# RH010_1.net
KiCad netlist of a schematic drawn in EAGLE
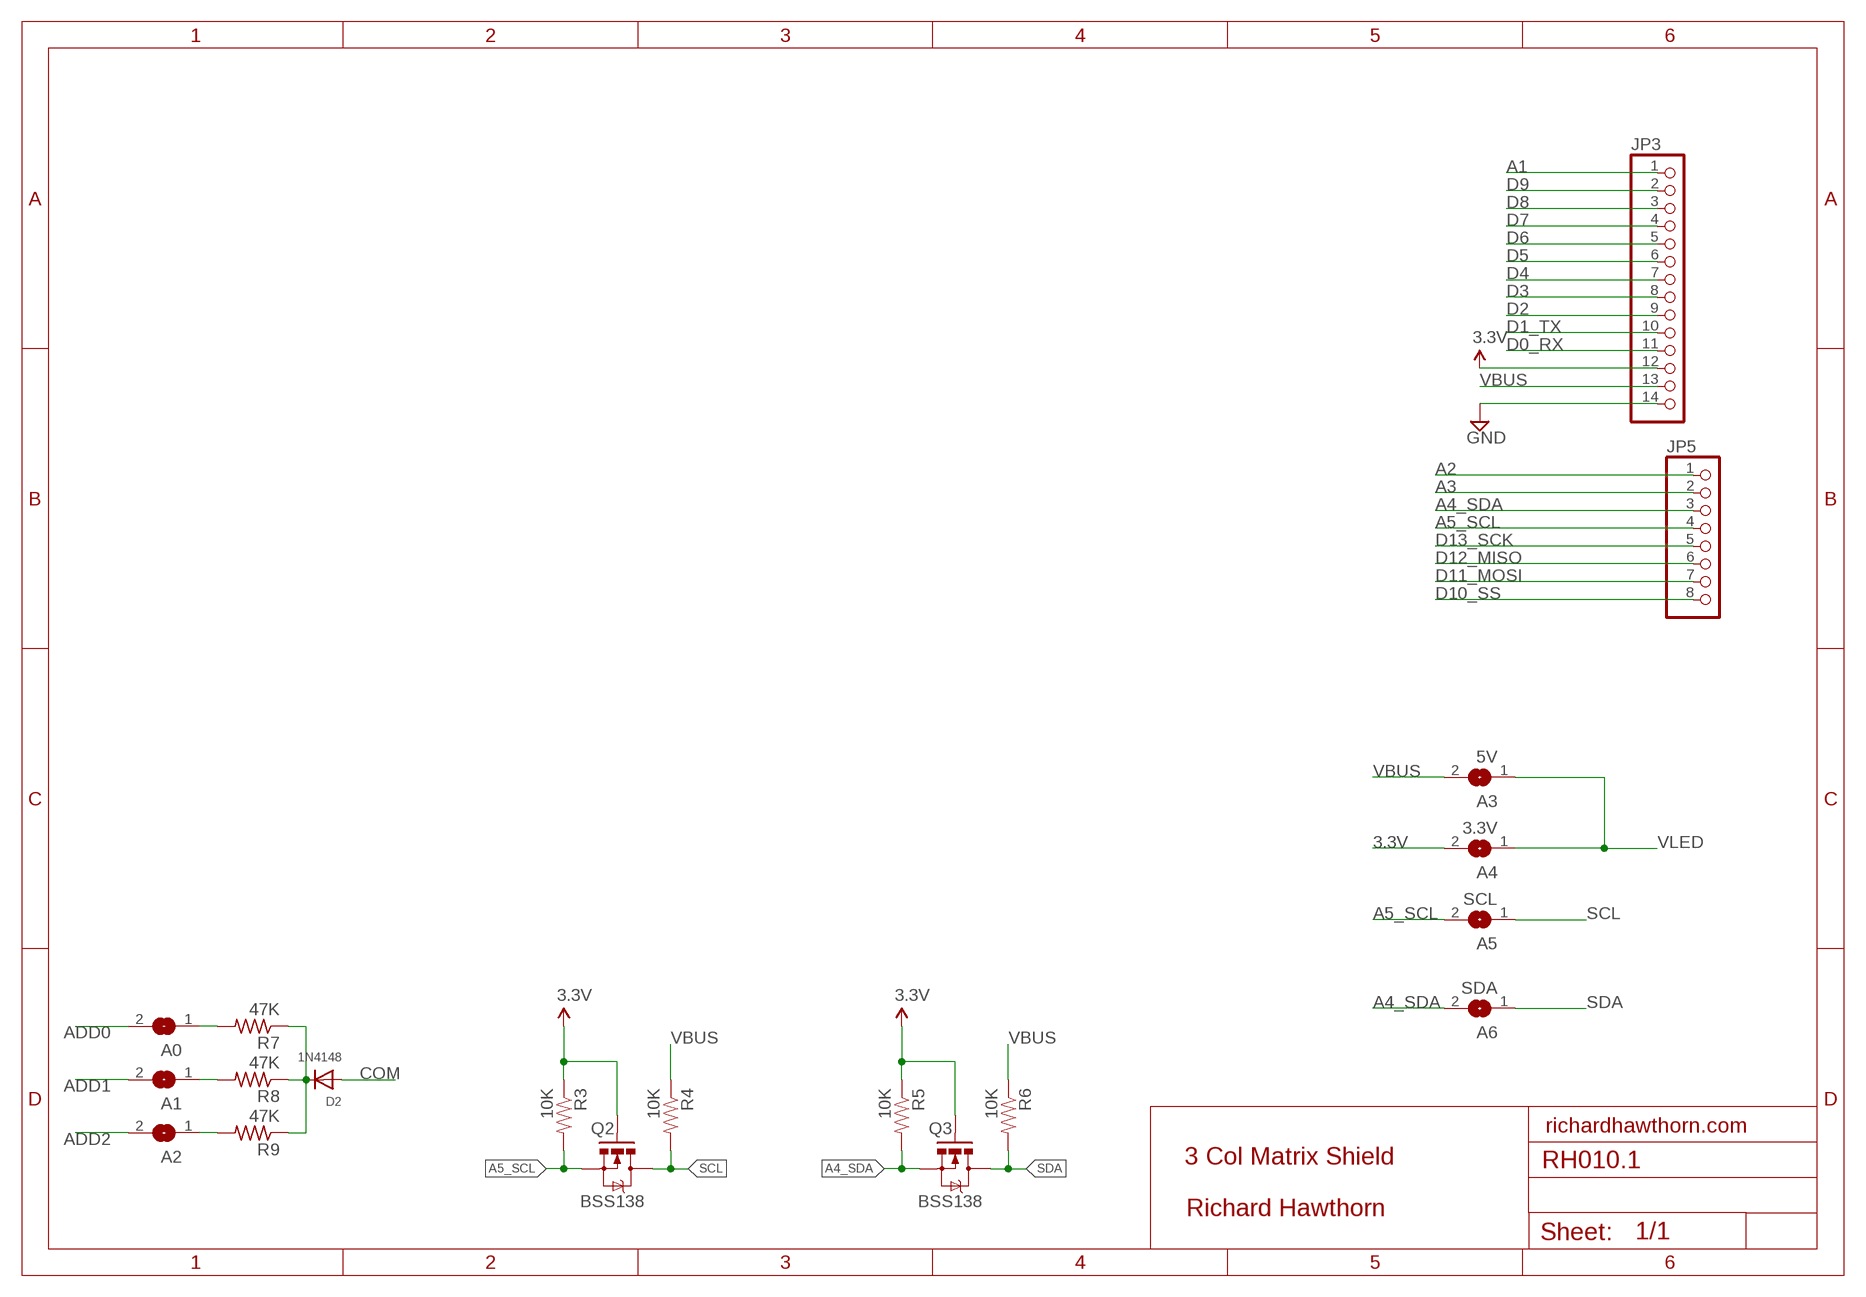
[diagram p0: schematic, sheet 1, part 1 of 2]
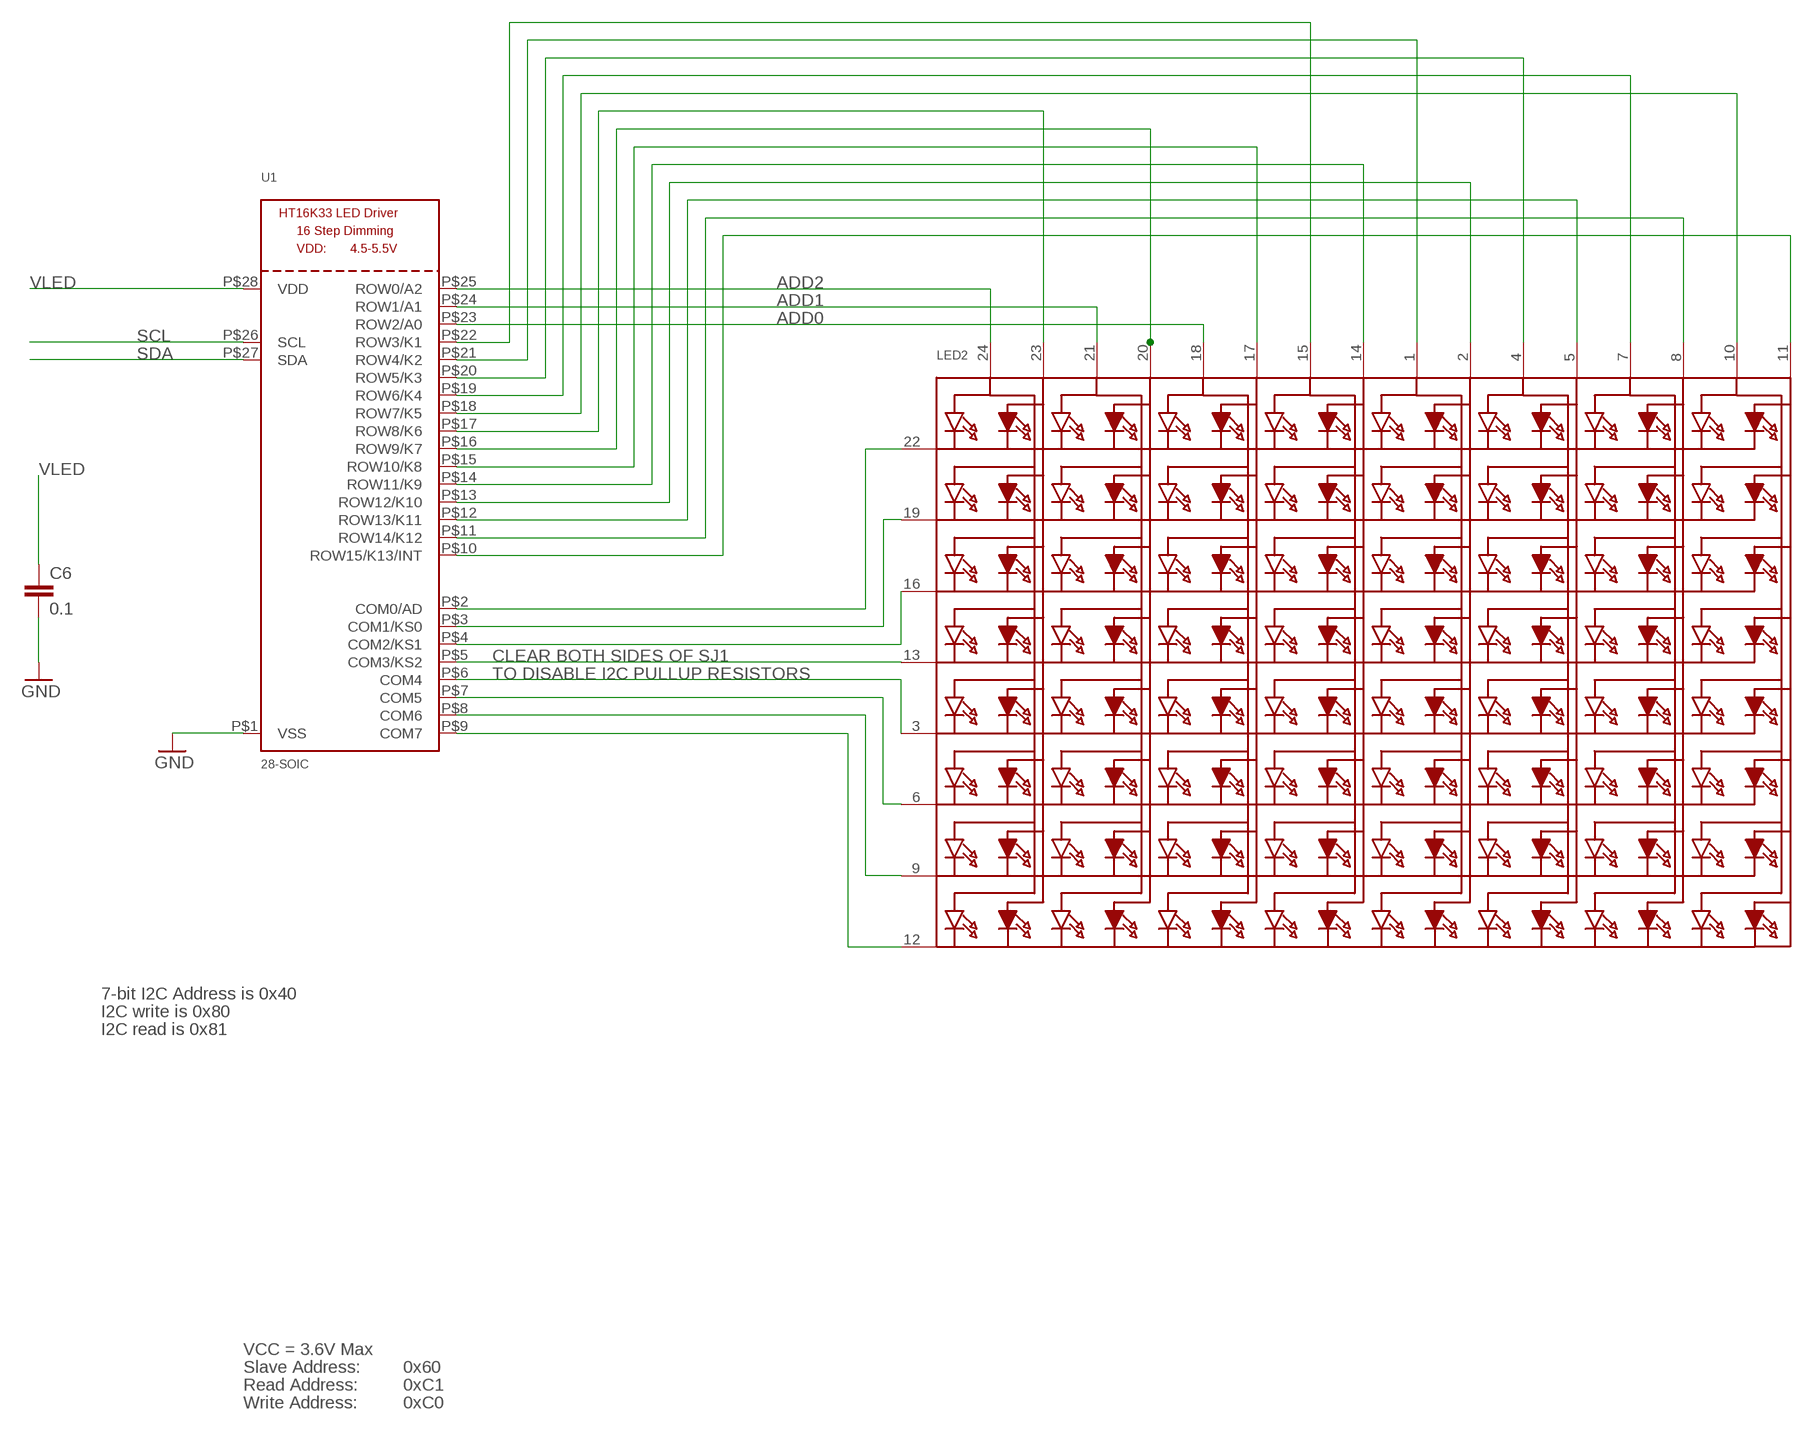
[diagram p1: schematic, sheet 1, part 2 of 2]

(export (version "E")
  (design (tool "Eeschema 10.0.6"))
  (components
    (comp (ref "A0")
      (value "SOLDERJUMPERREFLOW_NOPASTE")
      (footprint "eagle-import:SOLDERJUMPER_REFLOW_NOPASTE")
      (libsource (lib "eagle-import") (part "SOLDERJUMPERREFLOW_NOPASTE"))
    )
    (comp (ref "A1")
      (value "SOLDERJUMPERREFLOW_NOPASTE")
      (footprint "eagle-import:SOLDERJUMPER_REFLOW_NOPASTE")
      (libsource (lib "eagle-import") (part "SOLDERJUMPERREFLOW_NOPASTE"))
    )
    (comp (ref "A2")
      (value "SOLDERJUMPERREFLOW_NOPASTE")
      (footprint "eagle-import:SOLDERJUMPER_REFLOW_NOPASTE")
      (libsource (lib "eagle-import") (part "SOLDERJUMPERREFLOW_NOPASTE"))
    )
    (comp (ref "A3")
      (value "5V")
      (footprint "eagle-import:SOLDERJUMPER_REFLOW_NOPASTE")
      (libsource (lib "eagle-import") (part "SOLDERJUMPERREFLOW_NOPASTE"))
    )
    (comp (ref "A4")
      (value "3.3V")
      (footprint "eagle-import:SOLDERJUMPER_REFLOW_NOPASTE")
      (libsource (lib "eagle-import") (part "SOLDERJUMPERREFLOW_NOPASTE"))
    )
    (comp (ref "A5")
      (value "SCL")
      (footprint "eagle-import:SOLDERJUMPER_REFLOW_NOPASTE")
      (libsource (lib "eagle-import") (part "SOLDERJUMPERREFLOW_NOPASTE"))
    )
    (comp (ref "A6")
      (value "SDA")
      (footprint "eagle-import:SOLDERJUMPER_REFLOW_NOPASTE")
      (libsource (lib "eagle-import") (part "SOLDERJUMPERREFLOW_NOPASTE"))
    )
    (comp (ref "C6")
      (value "0.1")
      (footprint "eagle-import:0603-CAP")
      (libsource (lib "eagle-import") (part "CAP0603-CAP"))
    )
    (comp (ref "D2")
      (value "1N4148")
      (footprint "eagle-import:SOD-323F")
      (libsource (lib "eagle-import") (part "DIODESOD-323F"))
    )
    (comp (ref "JP3")
      (value "PINHD-1X14")
      (footprint "eagle-import:1X14")
      (libsource (lib "eagle-import") (part "PINHD-1X14"))
    )
    (comp (ref "JP5")
      (value "PINHD-1X8")
      (footprint "eagle-import:1X08")
      (libsource (lib "eagle-import") (part "PINHD-1X8"))
    )
    (comp (ref "LED2")
      (value "DISP_SEGMENT_8X8_BICOLOR_ROWCATHODEMI2A883XX")
      (footprint "eagle-import:SEGMENT_BICOL_BL-M12A883XX")
      (libsource (lib "eagle-import") (part "DISP_SEGMENT_8X8_BICOLOR_ROWCATHODEMI2A883XX"))
    )
    (comp (ref "Q2")
      (value "BSS138")
      (footprint "eagle-import:SOT23-3")
      (libsource (lib "eagle-import") (part "MOSFET-NCHANNELSMD"))
    )
    (comp (ref "Q3")
      (value "BSS138")
      (footprint "eagle-import:SOT23-3")
      (libsource (lib "eagle-import") (part "MOSFET-NCHANNELSMD"))
    )
    (comp (ref "R3")
      (value "10K")
      (footprint "eagle-import:0603-RES")
      (libsource (lib "eagle-import") (part "RESISTOR0603-RES"))
    )
    (comp (ref "R4")
      (value "10K")
      (footprint "eagle-import:0603-RES")
      (libsource (lib "eagle-import") (part "RESISTOR0603-RES"))
    )
    (comp (ref "R5")
      (value "10K")
      (footprint "eagle-import:0603-RES")
      (libsource (lib "eagle-import") (part "RESISTOR0603-RES"))
    )
    (comp (ref "R6")
      (value "10K")
      (footprint "eagle-import:0603-RES")
      (libsource (lib "eagle-import") (part "RESISTOR0603-RES"))
    )
    (comp (ref "R7")
      (value "47K")
      (footprint "eagle-import:R0805")
      (libsource (lib "eagle-import") (part "R-US_R0805"))
    )
    (comp (ref "R8")
      (value "47K")
      (footprint "eagle-import:R0805")
      (libsource (lib "eagle-import") (part "R-US_R0805"))
    )
    (comp (ref "R9")
      (value "47K")
      (footprint "eagle-import:R0805")
      (libsource (lib "eagle-import") (part "R-US_R0805"))
    )
    (comp (ref "U1")
      (value "28-SOIC")
      (footprint "eagle-import:SOP28_300MIL")
      (libsource (lib "eagle-import") (part "HT16K33_SOP28"))
    )
  )
  (nets
    (net (code "1") (name "/A1") (class "Default")
      (node (ref "JP3") (pin "1") (pinfunction "1_1") (pintype "passive"))
    )
    (net (code "2") (name "/A2") (class "Default")
      (node (ref "JP5") (pin "1") (pinfunction "1_1") (pintype "passive"))
    )
    (net (code "3") (name "/A3") (class "Default")
      (node (ref "JP5") (pin "2") (pinfunction "2_2") (pintype "passive"))
    )
    (net (code "4") (name "/ADD0") (class "Default")
      (node (ref "A0") (pin "2") (pinfunction "2_2") (pintype "passive"))
      (node (ref "LED2") (pin "18") (pinfunction "A5_18") (pintype "bidirectional"))
      (node (ref "U1") (pin "P$23") (pinfunction "ROW2/A0_P$23") (pintype "bidirectional"))
    )
    (net (code "5") (name "/ADD1") (class "Default")
      (node (ref "A1") (pin "2") (pinfunction "2_2") (pintype "passive"))
      (node (ref "LED2") (pin "21") (pinfunction "A3_21") (pintype "bidirectional"))
      (node (ref "U1") (pin "P$24") (pinfunction "ROW1/A1_P$24") (pintype "bidirectional"))
    )
    (net (code "6") (name "/ADD2") (class "Default")
      (node (ref "A2") (pin "2") (pinfunction "2_2") (pintype "passive"))
      (node (ref "LED2") (pin "24") (pinfunction "A1_24") (pintype "bidirectional"))
      (node (ref "U1") (pin "P$25") (pinfunction "ROW0/A2_P$25") (pintype "bidirectional"))
    )
    (net (code "7") (name "/COM") (class "Default")
      (node (ref "D2") (pin "A") (pinfunction "A_A") (pintype "passive"))
      (node (ref "LED2") (pin "22") (pinfunction "K1_22") (pintype "bidirectional"))
      (node (ref "U1") (pin "P$2") (pinfunction "COM0/AD_P$2") (pintype "bidirectional"))
    )
    (net (code "8") (name "/D0_RX") (class "Default")
      (node (ref "JP3") (pin "11") (pinfunction "11_11") (pintype "passive"))
    )
    (net (code "9") (name "/D1_TX") (class "Default")
      (node (ref "JP3") (pin "10") (pinfunction "10_10") (pintype "passive"))
    )
    (net (code "10") (name "/D2") (class "Default")
      (node (ref "JP3") (pin "9") (pinfunction "9_9") (pintype "passive"))
    )
    (net (code "11") (name "/D3") (class "Default")
      (node (ref "JP3") (pin "8") (pinfunction "8_8") (pintype "passive"))
    )
    (net (code "12") (name "/D4") (class "Default")
      (node (ref "JP3") (pin "7") (pinfunction "7_7") (pintype "passive"))
    )
    (net (code "13") (name "/D5") (class "Default")
      (node (ref "JP3") (pin "6") (pinfunction "6_6") (pintype "passive"))
    )
    (net (code "14") (name "/D6") (class "Default")
      (node (ref "JP3") (pin "5") (pinfunction "5_5") (pintype "passive"))
    )
    (net (code "15") (name "/D7") (class "Default")
      (node (ref "JP3") (pin "4") (pinfunction "4_4") (pintype "passive"))
    )
    (net (code "16") (name "/D8") (class "Default")
      (node (ref "JP3") (pin "3") (pinfunction "3_3") (pintype "passive"))
    )
    (net (code "17") (name "/D9") (class "Default")
      (node (ref "JP3") (pin "2") (pinfunction "2_2") (pintype "passive"))
    )
    (net (code "18") (name "/D10_SS") (class "Default")
      (node (ref "JP5") (pin "8") (pinfunction "8_8") (pintype "passive"))
    )
    (net (code "19") (name "/D11_MOSI") (class "Default")
      (node (ref "JP5") (pin "7") (pinfunction "7_7") (pintype "passive"))
    )
    (net (code "20") (name "/D12_MISO") (class "Default")
      (node (ref "JP5") (pin "6") (pinfunction "6_6") (pintype "passive"))
    )
    (net (code "21") (name "/D13_SCK") (class "Default")
      (node (ref "JP5") (pin "5") (pinfunction "5_5") (pintype "passive"))
    )
    (net (code "22") (name "/VBUS") (class "Default")
      (node (ref "A3") (pin "2") (pinfunction "2_2") (pintype "passive"))
      (node (ref "JP3") (pin "13") (pinfunction "13_13") (pintype "passive"))
      (node (ref "R4") (pin "1") (pinfunction "1_1") (pintype "passive"))
      (node (ref "R6") (pin "1") (pinfunction "1_1") (pintype "passive"))
    )
    (net (code "23") (name "/VLED") (class "Default")
      (node (ref "A3") (pin "1") (pinfunction "1_1") (pintype "passive"))
      (node (ref "A4") (pin "1") (pinfunction "1_1") (pintype "passive"))
      (node (ref "C6") (pin "1") (pinfunction "1_1") (pintype "passive"))
      (node (ref "U1") (pin "P$28") (pinfunction "VDD_P$28") (pintype "bidirectional"))
    )
    (net (code "24") (name "3.3V") (class "Default")
      (node (ref "A4") (pin "2") (pinfunction "2_2") (pintype "passive"))
      (node (ref "JP3") (pin "12") (pinfunction "12_12") (pintype "passive"))
      (node (ref "Q2") (pin "1") (pinfunction "G_1") (pintype "passive"))
      (node (ref "Q3") (pin "1") (pinfunction "G_1") (pintype "passive"))
      (node (ref "R3") (pin "1") (pinfunction "1_1") (pintype "passive"))
      (node (ref "R5") (pin "1") (pinfunction "1_1") (pintype "passive"))
    )
    (net (code "25") (name "A4_SDA") (class "Default")
      (node (ref "A6") (pin "2") (pinfunction "2_2") (pintype "passive"))
      (node (ref "JP5") (pin "3") (pinfunction "3_3") (pintype "passive"))
      (node (ref "Q3") (pin "2") (pinfunction "S_2") (pintype "passive"))
      (node (ref "R5") (pin "2") (pinfunction "2_2") (pintype "passive"))
    )
    (net (code "26") (name "A5_SCL") (class "Default")
      (node (ref "A5") (pin "2") (pinfunction "2_2") (pintype "passive"))
      (node (ref "JP5") (pin "4") (pinfunction "4_4") (pintype "passive"))
      (node (ref "Q2") (pin "2") (pinfunction "S_2") (pintype "passive"))
      (node (ref "R3") (pin "2") (pinfunction "2_2") (pintype "passive"))
    )
    (net (code "27") (name "GND") (class "Default")
      (node (ref "C6") (pin "2") (pinfunction "2_2") (pintype "passive"))
      (node (ref "JP3") (pin "14") (pinfunction "14_14") (pintype "passive"))
      (node (ref "U1") (pin "P$1") (pinfunction "VSS_P$1") (pintype "bidirectional"))
    )
    (net (code "28") (name "Net-(A0-Pad1)") (class "Default")
      (node (ref "A0") (pin "1") (pinfunction "1_1") (pintype "passive"))
      (node (ref "R7") (pin "2") (pinfunction "2_2") (pintype "passive"))
    )
    (net (code "29") (name "Net-(A1-Pad1)") (class "Default")
      (node (ref "A1") (pin "1") (pinfunction "1_1") (pintype "passive"))
      (node (ref "R8") (pin "2") (pinfunction "2_2") (pintype "passive"))
    )
    (net (code "30") (name "Net-(A2-Pad1)") (class "Default")
      (node (ref "A2") (pin "1") (pinfunction "1_1") (pintype "passive"))
      (node (ref "R9") (pin "2") (pinfunction "2_2") (pintype "passive"))
    )
    (net (code "31") (name "Net-(D2-PadC)") (class "Default")
      (node (ref "D2") (pin "C") (pinfunction "C_C") (pintype "passive"))
      (node (ref "R7") (pin "1") (pinfunction "1_1") (pintype "passive"))
      (node (ref "R8") (pin "1") (pinfunction "1_1") (pintype "passive"))
      (node (ref "R9") (pin "1") (pinfunction "1_1") (pintype "passive"))
    )
    (net (code "32") (name "Net-(LED2-A2)") (class "Default")
      (node (ref "LED2") (pin "23") (pinfunction "A2_23") (pintype "bidirectional"))
      (node (ref "U1") (pin "P$17") (pinfunction "ROW8/K6_P$17") (pintype "bidirectional"))
    )
    (net (code "33") (name "Net-(LED2-A4)") (class "Default")
      (node (ref "LED2") (pin "20") (pinfunction "A4_20") (pintype "bidirectional"))
      (node (ref "U1") (pin "P$16") (pinfunction "ROW9/K7_P$16") (pintype "bidirectional"))
    )
    (net (code "34") (name "Net-(LED2-A6)") (class "Default")
      (node (ref "LED2") (pin "17") (pinfunction "A6_17") (pintype "bidirectional"))
      (node (ref "U1") (pin "P$15") (pinfunction "ROW10/K8_P$15") (pintype "bidirectional"))
    )
    (net (code "35") (name "Net-(LED2-A7)") (class "Default")
      (node (ref "LED2") (pin "15") (pinfunction "A7_15") (pintype "bidirectional"))
      (node (ref "U1") (pin "P$22") (pinfunction "ROW3/K1_P$22") (pintype "bidirectional"))
    )
    (net (code "36") (name "Net-(LED2-A8)") (class "Default")
      (node (ref "LED2") (pin "14") (pinfunction "A8_14") (pintype "bidirectional"))
      (node (ref "U1") (pin "P$14") (pinfunction "ROW11/K9_P$14") (pintype "bidirectional"))
    )
    (net (code "37") (name "Net-(LED2-A9)") (class "Default")
      (node (ref "LED2") (pin "1") (pinfunction "A9_1") (pintype "bidirectional"))
      (node (ref "U1") (pin "P$21") (pinfunction "ROW4/K2_P$21") (pintype "bidirectional"))
    )
    (net (code "38") (name "Net-(LED2-A10)") (class "Default")
      (node (ref "LED2") (pin "2") (pinfunction "A10_2") (pintype "bidirectional"))
      (node (ref "U1") (pin "P$13") (pinfunction "ROW12/K10_P$13") (pintype "bidirectional"))
    )
    (net (code "39") (name "Net-(LED2-A11)") (class "Default")
      (node (ref "LED2") (pin "4") (pinfunction "A11_4") (pintype "bidirectional"))
      (node (ref "U1") (pin "P$20") (pinfunction "ROW5/K3_P$20") (pintype "bidirectional"))
    )
    (net (code "40") (name "Net-(LED2-A12)") (class "Default")
      (node (ref "LED2") (pin "5") (pinfunction "A12_5") (pintype "bidirectional"))
      (node (ref "U1") (pin "P$12") (pinfunction "ROW13/K11_P$12") (pintype "bidirectional"))
    )
    (net (code "41") (name "Net-(LED2-A13)") (class "Default")
      (node (ref "LED2") (pin "7") (pinfunction "A13_7") (pintype "bidirectional"))
      (node (ref "U1") (pin "P$19") (pinfunction "ROW6/K4_P$19") (pintype "bidirectional"))
    )
    (net (code "42") (name "Net-(LED2-A14)") (class "Default")
      (node (ref "LED2") (pin "8") (pinfunction "A14_8") (pintype "bidirectional"))
      (node (ref "U1") (pin "P$11") (pinfunction "ROW14/K12_P$11") (pintype "bidirectional"))
    )
    (net (code "43") (name "Net-(LED2-A15)") (class "Default")
      (node (ref "LED2") (pin "10") (pinfunction "A15_10") (pintype "bidirectional"))
      (node (ref "U1") (pin "P$18") (pinfunction "ROW7/K5_P$18") (pintype "bidirectional"))
    )
    (net (code "44") (name "Net-(LED2-A16)") (class "Default")
      (node (ref "LED2") (pin "11") (pinfunction "A16_11") (pintype "bidirectional"))
      (node (ref "U1") (pin "P$10") (pinfunction "ROW15/K13/INT_P$10") (pintype "bidirectional"))
    )
    (net (code "45") (name "Net-(LED2-K2)") (class "Default")
      (node (ref "LED2") (pin "19") (pinfunction "K2_19") (pintype "bidirectional"))
      (node (ref "U1") (pin "P$3") (pinfunction "COM1/KS0_P$3") (pintype "bidirectional"))
    )
    (net (code "46") (name "Net-(LED2-K3)") (class "Default")
      (node (ref "LED2") (pin "16") (pinfunction "K3_16") (pintype "bidirectional"))
      (node (ref "U1") (pin "P$4") (pinfunction "COM2/KS1_P$4") (pintype "bidirectional"))
    )
    (net (code "47") (name "Net-(LED2-K4)") (class "Default")
      (node (ref "LED2") (pin "13") (pinfunction "K4_13") (pintype "bidirectional"))
      (node (ref "U1") (pin "P$5") (pinfunction "COM3/KS2_P$5") (pintype "bidirectional"))
    )
    (net (code "48") (name "Net-(LED2-K5)") (class "Default")
      (node (ref "LED2") (pin "3") (pinfunction "K5_3") (pintype "bidirectional"))
      (node (ref "U1") (pin "P$6") (pinfunction "COM4_P$6") (pintype "bidirectional"))
    )
    (net (code "49") (name "Net-(LED2-K6)") (class "Default")
      (node (ref "LED2") (pin "6") (pinfunction "K6_6") (pintype "bidirectional"))
      (node (ref "U1") (pin "P$7") (pinfunction "COM5_P$7") (pintype "bidirectional"))
    )
    (net (code "50") (name "Net-(LED2-K7)") (class "Default")
      (node (ref "LED2") (pin "9") (pinfunction "K7_9") (pintype "bidirectional"))
      (node (ref "U1") (pin "P$8") (pinfunction "COM6_P$8") (pintype "bidirectional"))
    )
    (net (code "51") (name "Net-(LED2-K8)") (class "Default")
      (node (ref "LED2") (pin "12") (pinfunction "K8_12") (pintype "bidirectional"))
      (node (ref "U1") (pin "P$9") (pinfunction "COM7_P$9") (pintype "bidirectional"))
    )
    (net (code "52") (name "SCL") (class "Default")
      (node (ref "A5") (pin "1") (pinfunction "1_1") (pintype "passive"))
      (node (ref "Q2") (pin "3") (pinfunction "D_3") (pintype "passive"))
      (node (ref "R4") (pin "2") (pinfunction "2_2") (pintype "passive"))
      (node (ref "U1") (pin "P$26") (pinfunction "SCL_P$26") (pintype "bidirectional"))
    )
    (net (code "53") (name "SDA") (class "Default")
      (node (ref "A6") (pin "1") (pinfunction "1_1") (pintype "passive"))
      (node (ref "Q3") (pin "3") (pinfunction "D_3") (pintype "passive"))
      (node (ref "R6") (pin "2") (pinfunction "2_2") (pintype "passive"))
      (node (ref "U1") (pin "P$27") (pinfunction "SDA_P$27") (pintype "bidirectional"))
    )
  )
)
